# IO4SignalDriver-Small.net
KiCad netlist of a schematic drawn in EAGLE
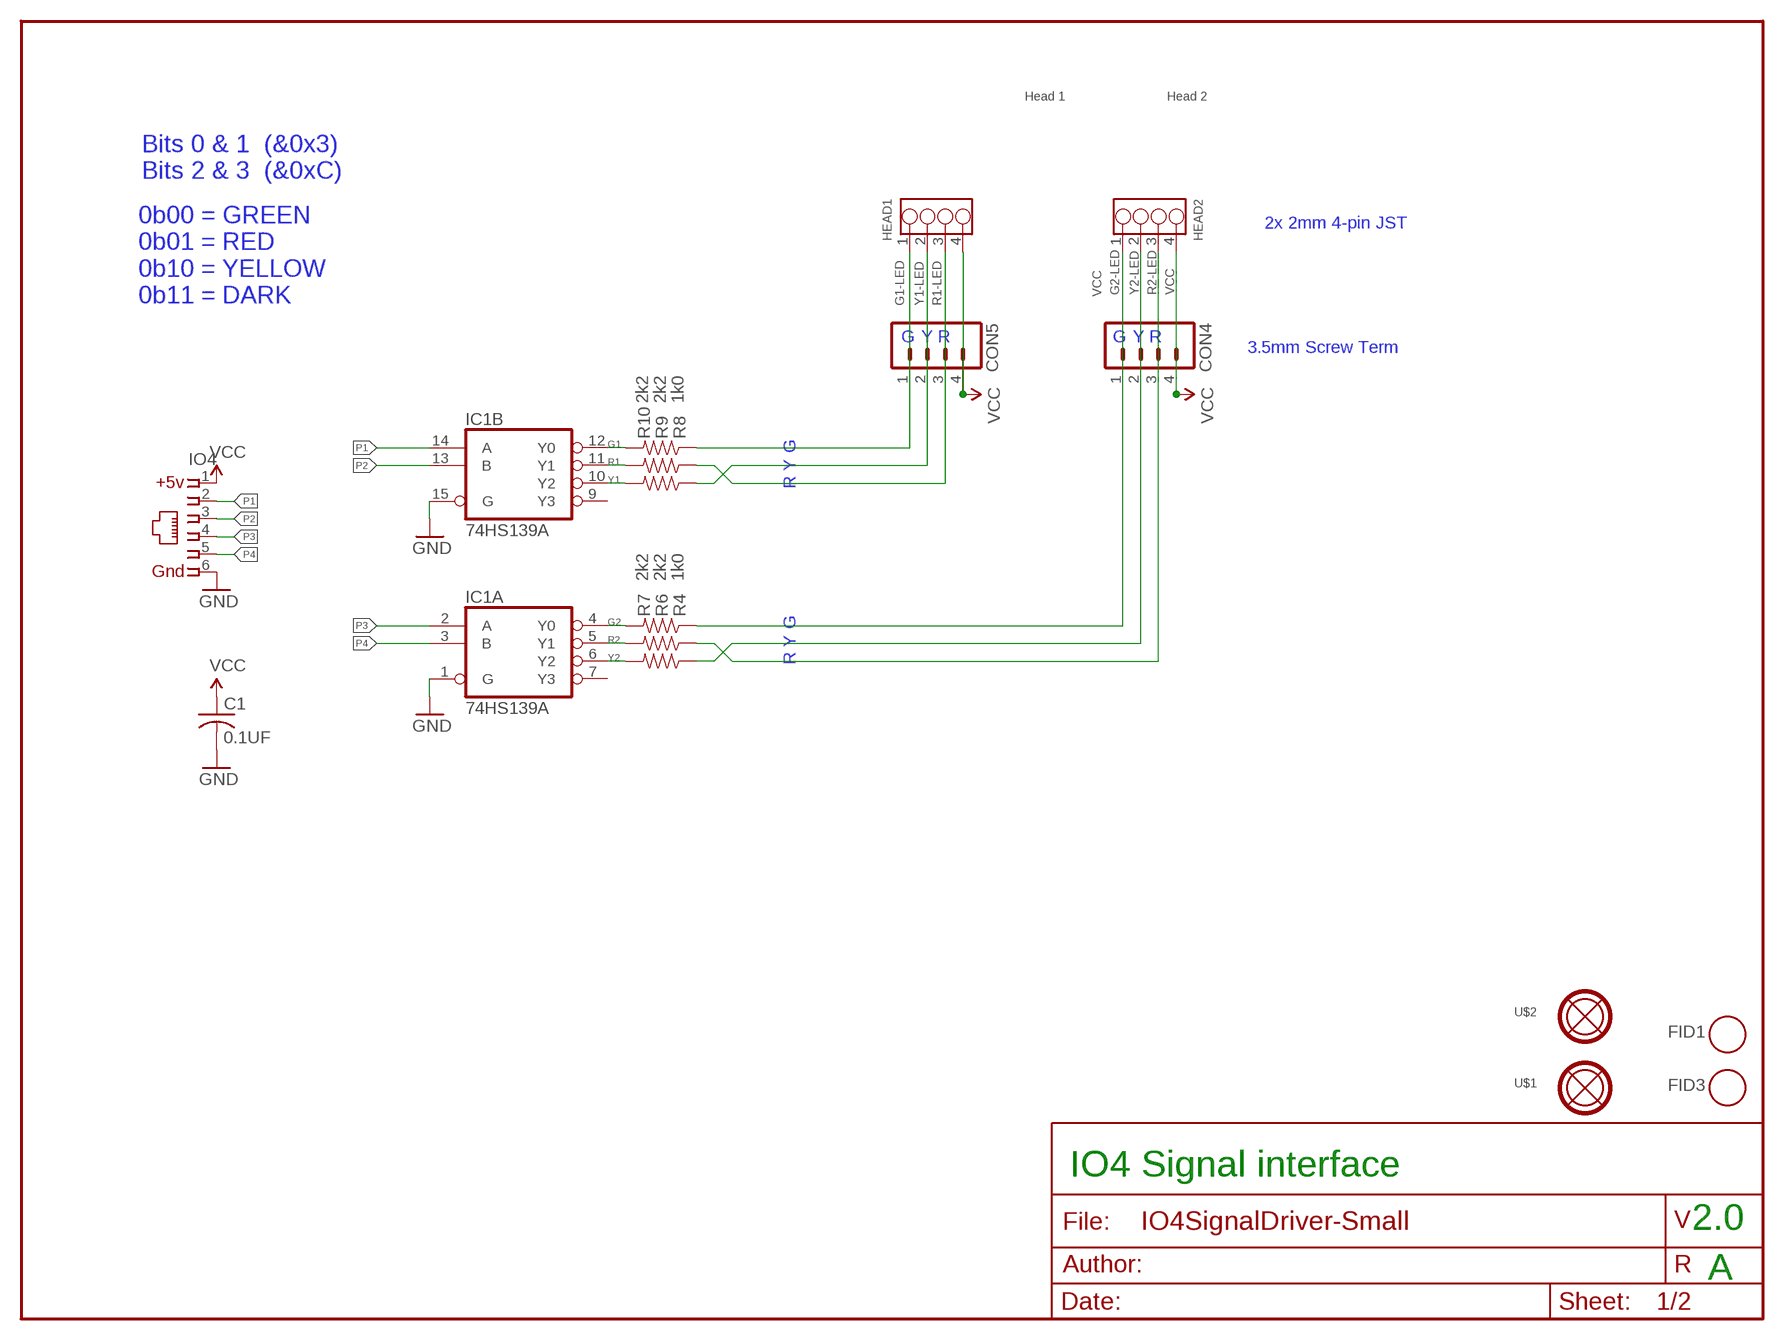
[diagram p0: schematic, sheet 1]
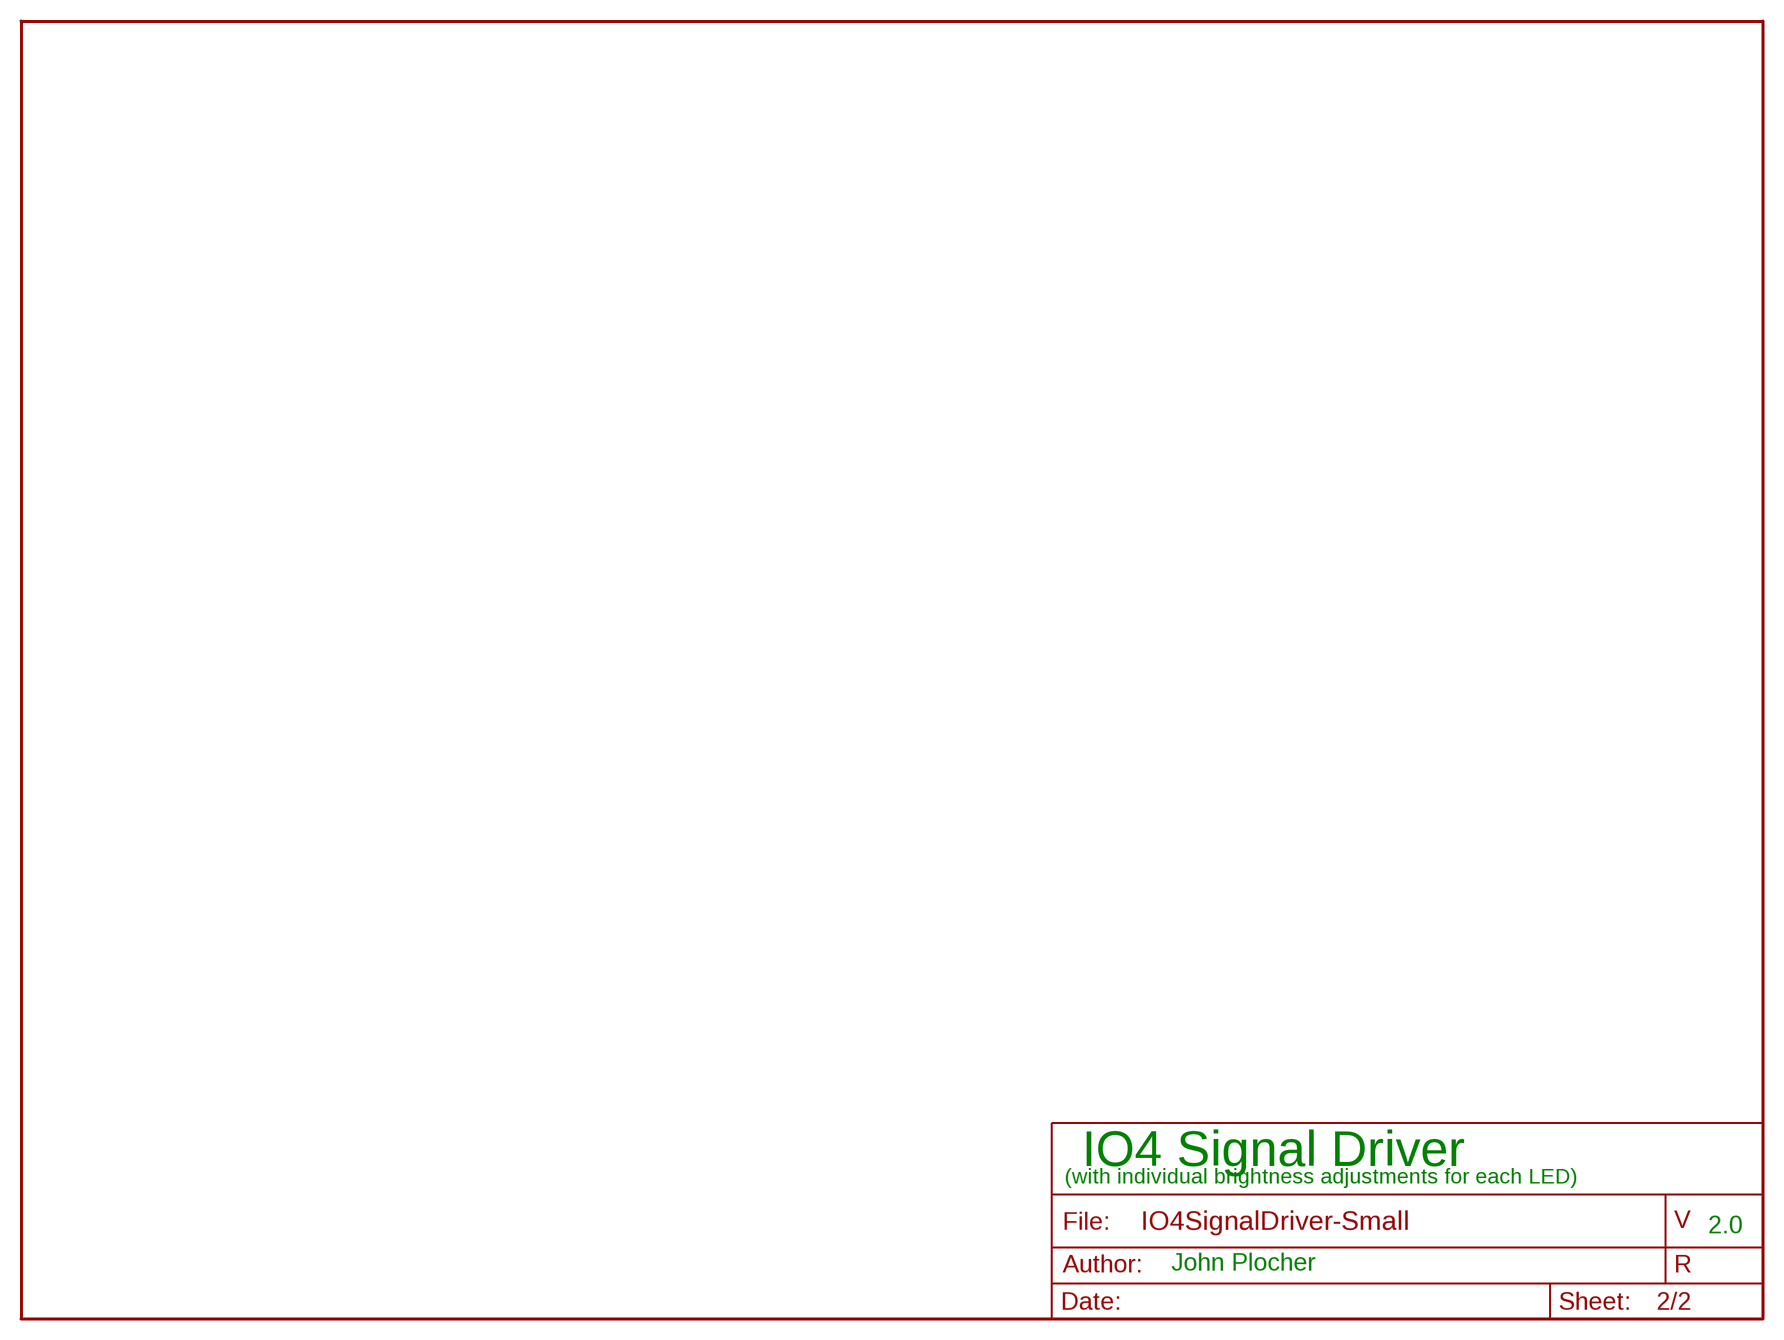
[diagram p1: schematic, sheet 2]

(export (version "E")
  (design (tool "Eeschema 10.0.6"))
  (components
    (comp (ref "C1")
      (value "0.1UF")
      (footprint "eagle-import:0805-CAP")
      (libsource (lib "eagle-import") (part "CAP0805"))
    )
    (comp (ref "CON4")
      (value "CONNECTOR-M04SCREW")
      (footprint "eagle-import:SCREWTERMINAL-3.5MM-4")
      (libsource (lib "eagle-import") (part "CONNECTOR-M04SCREW"))
    )
    (comp (ref "CON5")
      (value "CONNECTOR-M04SCREW")
      (footprint "eagle-import:SCREWTERMINAL-3.5MM-4")
      (libsource (lib "eagle-import") (part "CONNECTOR-M04SCREW"))
    )
    (comp (ref "FID1")
      (value "FIDUCIAL")
      (footprint "eagle-import:FIDUCIAL_1MM")
      (libsource (lib "eagle-import") (part "FIDUCIAL"))
    )
    (comp (ref "FID3")
      (value "FIDUCIAL")
      (footprint "eagle-import:FIDUCIAL_1MM")
      (libsource (lib "eagle-import") (part "FIDUCIAL"))
    )
    (comp (ref "HEAD1")
      (value "Head 1")
      (footprint "eagle-import:4P-2.0")
      (libsource (lib "eagle-import") (part "CONNECTOR-GROVE-4P-2.0-3470130P1"))
    )
    (comp (ref "HEAD2")
      (value "Head 2")
      (footprint "eagle-import:4P-2.0")
      (libsource (lib "eagle-import") (part "CONNECTOR-GROVE-4P-2.0-3470130P1"))
    )
    (comp (ref "IC1")
      (value "74HS139A")
      (footprint "eagle-import:SO16")
      (libsource (lib "eagle-import") (part "74139DLS"))
    )
    (comp (ref "IO4")
      (value "CONNECTOR-IO4INV")
      (footprint "eagle-import:RJ25-INVERTED")
      (libsource (lib "eagle-import") (part "CONNECTOR-IO4INV"))
    )
    (comp (ref "R4")
      (value "1k0")
      (footprint "eagle-import:0805-RES")
      (libsource (lib "eagle-import") (part "R0805-RES"))
    )
    (comp (ref "R6")
      (value "2k2")
      (footprint "eagle-import:0805-RES")
      (libsource (lib "eagle-import") (part "R0805-RES"))
    )
    (comp (ref "R7")
      (value "2k2")
      (footprint "eagle-import:0805-RES")
      (libsource (lib "eagle-import") (part "R0805-RES"))
    )
    (comp (ref "R8")
      (value "1k0")
      (footprint "eagle-import:0805-RES")
      (libsource (lib "eagle-import") (part "R0805-RES"))
    )
    (comp (ref "R9")
      (value "2k2")
      (footprint "eagle-import:0805-RES")
      (libsource (lib "eagle-import") (part "R0805-RES"))
    )
    (comp (ref "R10")
      (value "2k2")
      (footprint "eagle-import:0805-RES")
      (libsource (lib "eagle-import") (part "R0805-RES"))
    )
    (comp (ref "U$1")
      (value "MOUNTINGHOLE")
      (footprint "eagle-import:MOUNTINGHOLE")
      (libsource (lib "eagle-import") (part "MOUNTINGHOLE"))
    )
    (comp (ref "U$2")
      (value "MOUNTINGHOLE")
      (footprint "eagle-import:MOUNTINGHOLE")
      (libsource (lib "eagle-import") (part "MOUNTINGHOLE"))
    )
  )
  (nets
    (net (code "1") (name "G1") (class "Default")
      (node (ref "IC1") (pin "12") (pinfunction "Y0_12") (pintype "output"))
      (node (ref "R10") (pin "2") (pinfunction "2_2") (pintype "passive"))
    )
    (net (code "2") (name "G1-LED") (class "Default")
      (node (ref "CON5") (pin "1") (pinfunction "1_1") (pintype "passive"))
      (node (ref "HEAD1") (pin "1") (pinfunction "1_1") (pintype "bidirectional"))
      (node (ref "R10") (pin "1") (pinfunction "1_1") (pintype "passive"))
    )
    (net (code "3") (name "G2") (class "Default")
      (node (ref "IC1") (pin "4") (pinfunction "Y0_4") (pintype "output"))
      (node (ref "R7") (pin "2") (pinfunction "2_2") (pintype "passive"))
    )
    (net (code "4") (name "G2-LED") (class "Default")
      (node (ref "CON4") (pin "1") (pinfunction "1_1") (pintype "passive"))
      (node (ref "HEAD2") (pin "1") (pinfunction "1_1") (pintype "bidirectional"))
      (node (ref "R7") (pin "1") (pinfunction "1_1") (pintype "passive"))
    )
    (net (code "5") (name "GND") (class "Default")
      (node (ref "C1") (pin "2") (pinfunction "2_2") (pintype "passive"))
      (node (ref "IC1") (pin "1") (pinfunction "G_1") (pintype "input"))
      (node (ref "IC1") (pin "15") (pinfunction "G_15") (pintype "input"))
      (node (ref "IO4") (pin "6") (pinfunction "6_6") (pintype "power_in"))
    )
    (net (code "6") (name "P1") (class "Default")
      (node (ref "IC1") (pin "14") (pinfunction "A_14") (pintype "input"))
      (node (ref "IO4") (pin "2") (pinfunction "2_2") (pintype "passive"))
    )
    (net (code "7") (name "P2") (class "Default")
      (node (ref "IC1") (pin "13") (pinfunction "B_13") (pintype "input"))
      (node (ref "IO4") (pin "3") (pinfunction "3_3") (pintype "passive"))
    )
    (net (code "8") (name "P3") (class "Default")
      (node (ref "IC1") (pin "2") (pinfunction "A_2") (pintype "input"))
      (node (ref "IO4") (pin "4") (pinfunction "4_4") (pintype "passive"))
    )
    (net (code "9") (name "P4") (class "Default")
      (node (ref "IC1") (pin "3") (pinfunction "B_3") (pintype "input"))
      (node (ref "IO4") (pin "5") (pinfunction "5_5") (pintype "passive"))
    )
    (net (code "10") (name "R1") (class "Default")
      (node (ref "IC1") (pin "11") (pinfunction "Y1_11") (pintype "output"))
      (node (ref "R9") (pin "2") (pinfunction "2_2") (pintype "passive"))
    )
    (net (code "11") (name "R1-LED") (class "Default")
      (node (ref "CON5") (pin "3") (pinfunction "3_3") (pintype "passive"))
      (node (ref "HEAD1") (pin "3") (pinfunction "3_3") (pintype "bidirectional"))
      (node (ref "R9") (pin "1") (pinfunction "1_1") (pintype "passive"))
    )
    (net (code "12") (name "R2") (class "Default")
      (node (ref "IC1") (pin "5") (pinfunction "Y1_5") (pintype "output"))
      (node (ref "R6") (pin "2") (pinfunction "2_2") (pintype "passive"))
    )
    (net (code "13") (name "R2-LED") (class "Default")
      (node (ref "CON4") (pin "3") (pinfunction "3_3") (pintype "passive"))
      (node (ref "HEAD2") (pin "3") (pinfunction "3_3") (pintype "bidirectional"))
      (node (ref "R6") (pin "1") (pinfunction "1_1") (pintype "passive"))
    )
    (net (code "14") (name "VCC") (class "Default")
      (node (ref "C1") (pin "1") (pinfunction "1_1") (pintype "passive"))
      (node (ref "CON4") (pin "4") (pinfunction "4_4") (pintype "passive"))
      (node (ref "CON5") (pin "4") (pinfunction "4_4") (pintype "passive"))
      (node (ref "HEAD1") (pin "4") (pinfunction "4_4") (pintype "bidirectional"))
      (node (ref "HEAD2") (pin "4") (pinfunction "4_4") (pintype "bidirectional"))
      (node (ref "IO4") (pin "1") (pinfunction "1_1") (pintype "power_in"))
    )
    (net (code "15") (name "Y1") (class "Default")
      (node (ref "IC1") (pin "10") (pinfunction "Y2_10") (pintype "output"))
      (node (ref "R8") (pin "2") (pinfunction "2_2") (pintype "passive"))
    )
    (net (code "16") (name "Y1-LED") (class "Default")
      (node (ref "CON5") (pin "2") (pinfunction "2_2") (pintype "passive"))
      (node (ref "HEAD1") (pin "2") (pinfunction "2_2") (pintype "bidirectional"))
      (node (ref "R8") (pin "1") (pinfunction "1_1") (pintype "passive"))
    )
    (net (code "17") (name "Y2") (class "Default")
      (node (ref "IC1") (pin "6") (pinfunction "Y2_6") (pintype "output"))
      (node (ref "R4") (pin "2") (pinfunction "2_2") (pintype "passive"))
    )
    (net (code "18") (name "Y2-LED") (class "Default")
      (node (ref "CON4") (pin "2") (pinfunction "2_2") (pintype "passive"))
      (node (ref "HEAD2") (pin "2") (pinfunction "2_2") (pintype "bidirectional"))
      (node (ref "R4") (pin "1") (pinfunction "1_1") (pintype "passive"))
    )
    (net (code "19") (name "unconnected-(IC1A-Y3-Pad7)") (class "Default")
      (node (ref "IC1") (pin "7") (pinfunction "Y3_7") (pintype "output"))
    )
    (net (code "20") (name "unconnected-(IC1B-Y3-Pad9)") (class "Default")
      (node (ref "IC1") (pin "9") (pinfunction "Y3_9") (pintype "output"))
    )
  )
)
